# FPGA.net
KiCad netlist of a schematic drawn in Altium Designer
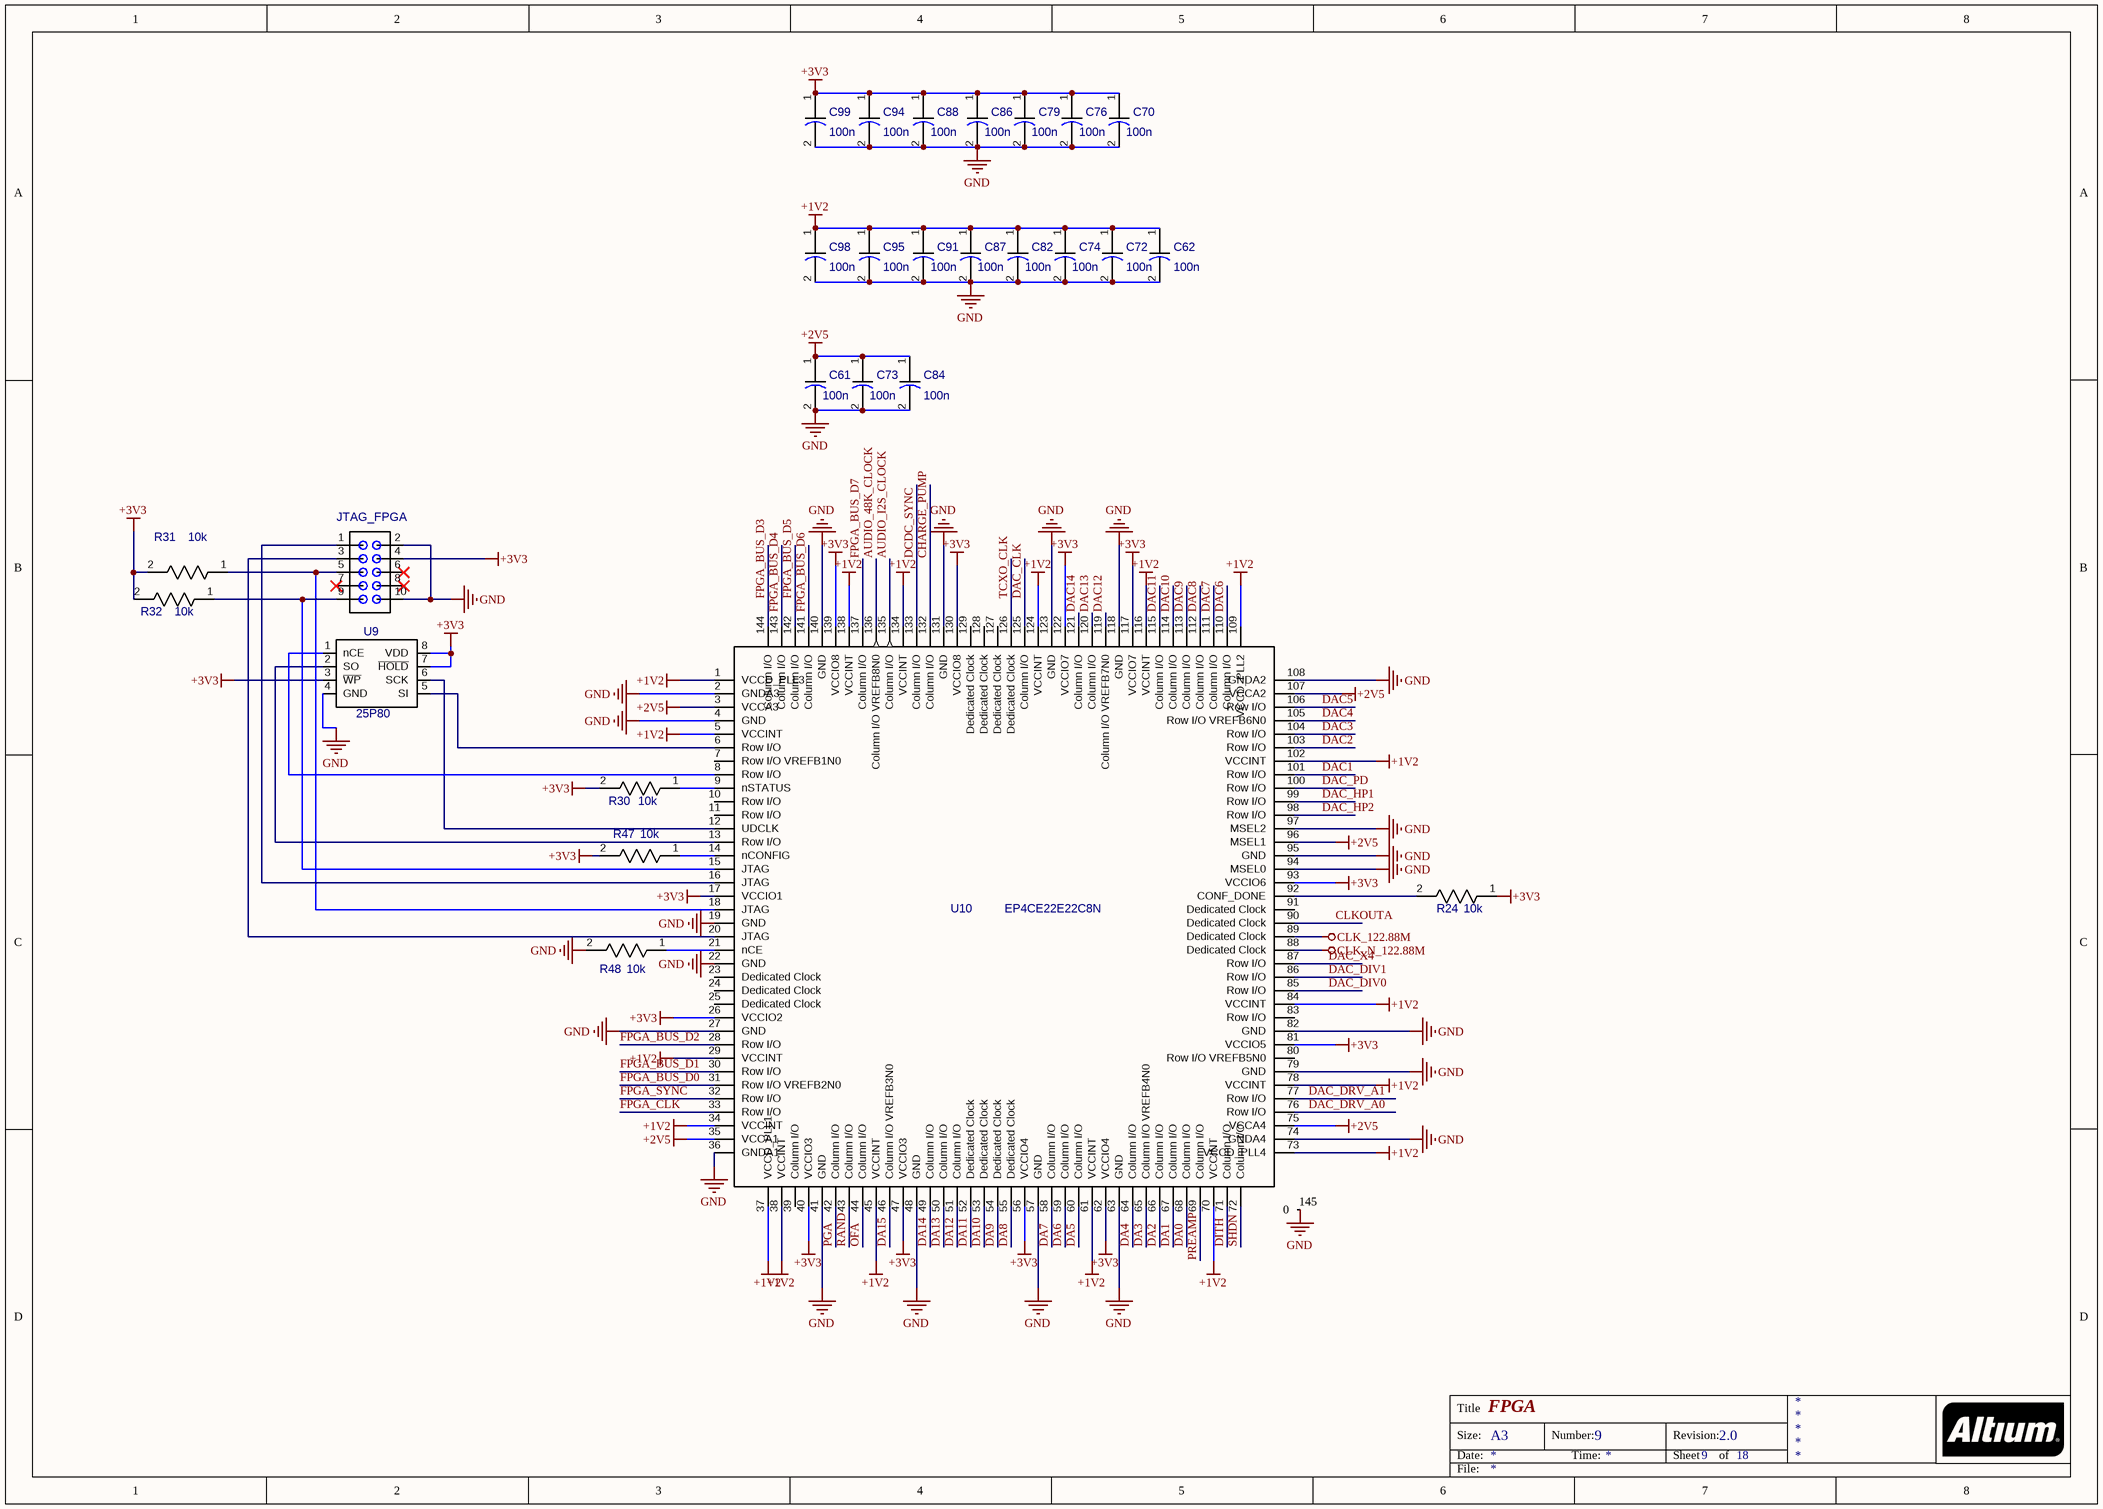
[diagram p0: FPGA.SchDoc]

(export (version "E")
  (design (tool "Eeschema 10.0.6"))
  (components
    (comp (ref "C61")
      (value "100n")
      (footprint "CAP_0805")
      (description "CAP_0805")
      (libsource (lib "*") (part "CAP_0805"))
    )
    (comp (ref "C62")
      (value "100n")
      (footprint "CAP_0805")
      (description "CAP_0805")
      (libsource (lib "*") (part "CAP_0805"))
    )
    (comp (ref "C70")
      (value "100n")
      (footprint "CAP_0805")
      (description "CAP_0805")
      (libsource (lib "*") (part "CAP_0805"))
    )
    (comp (ref "C72")
      (value "100n")
      (footprint "CAP_0805")
      (description "CAP_0805")
      (libsource (lib "*") (part "CAP_0805"))
    )
    (comp (ref "C73")
      (value "100n")
      (footprint "CAP_0805")
      (description "CAP_0805")
      (libsource (lib "*") (part "CAP_0805"))
    )
    (comp (ref "C74")
      (value "100n")
      (footprint "CAP_0805")
      (description "CAP_0805")
      (libsource (lib "*") (part "CAP_0805"))
    )
    (comp (ref "C76")
      (value "100n")
      (footprint "CAP_0805")
      (description "CAP_0805")
      (libsource (lib "*") (part "CAP_0805"))
    )
    (comp (ref "C79")
      (value "100n")
      (footprint "CAP_0805")
      (description "CAP_0805")
      (libsource (lib "*") (part "CAP_0805"))
    )
    (comp (ref "C82")
      (value "100n")
      (footprint "CAP_0805")
      (description "CAP_0805")
      (libsource (lib "*") (part "CAP_0805"))
    )
    (comp (ref "C84")
      (value "100n")
      (footprint "CAP_0805")
      (description "CAP_0805")
      (libsource (lib "*") (part "CAP_0805"))
    )
    (comp (ref "C86")
      (value "100n")
      (footprint "CAP_0805")
      (description "CAP_0805")
      (libsource (lib "*") (part "CAP_0805"))
    )
    (comp (ref "C87")
      (value "100n")
      (footprint "CAP_0805")
      (description "CAP_0805")
      (libsource (lib "*") (part "CAP_0805"))
    )
    (comp (ref "C88")
      (value "100n")
      (footprint "CAP_0805")
      (description "CAP_0805")
      (libsource (lib "*") (part "CAP_0805"))
    )
    (comp (ref "C91")
      (value "100n")
      (footprint "CAP_0805")
      (description "CAP_0805")
      (libsource (lib "*") (part "CAP_0805"))
    )
    (comp (ref "C94")
      (value "100n")
      (footprint "CAP_0805")
      (description "CAP_0805")
      (libsource (lib "*") (part "CAP_0805"))
    )
    (comp (ref "C95")
      (value "100n")
      (footprint "CAP_0805")
      (description "CAP_0805")
      (libsource (lib "*") (part "CAP_0805"))
    )
    (comp (ref "C98")
      (value "100n")
      (footprint "CAP_0805")
      (description "CAP_0805")
      (libsource (lib "*") (part "CAP_0805"))
    )
    (comp (ref "C99")
      (value "100n")
      (footprint "CAP_0805")
      (description "CAP_0805")
      (libsource (lib "*") (part "CAP_0805"))
    )
    (comp (ref "JTAG_FPGA")
      (value "~")
      (footprint "IDC10")
      (description "2*5 Pin")
      (libsource (lib "*") (part "IDC10"))
    )
    (comp (ref "R24")
      (value "10k")
      (footprint "RES_0805")
      (description "RES_0805")
      (libsource (lib "*") (part "RES_0805"))
    )
    (comp (ref "R30")
      (value "10k")
      (footprint "RES_0805")
      (description "RES_0805")
      (libsource (lib "*") (part "RES_0805"))
    )
    (comp (ref "R31")
      (value "10k")
      (footprint "RES_0805")
      (description "RES_0805")
      (libsource (lib "*") (part "RES_0805"))
    )
    (comp (ref "R32")
      (value "10k")
      (footprint "RES_0805")
      (description "RES_0805")
      (libsource (lib "*") (part "RES_0805"))
    )
    (comp (ref "R47")
      (value "10k")
      (footprint "RES_0805")
      (description "RES_0805")
      (libsource (lib "*") (part "RES_0805"))
    )
    (comp (ref "R48")
      (value "10k")
      (footprint "RES_0805")
      (description "RES_0805")
      (libsource (lib "*") (part "RES_0805"))
    )
    (comp (ref "U9") (value "25P80") (footprint "25P80") (libsource (lib "*") (part "25P80")))
    (comp (ref "U10")
      (value "EP4CE22E22C8N")
      (footprint "QFP144-20-2222A")
      (libsource (lib "*") (part "EP4CE22E22C8N"))
    )
  )
  (nets
    (net (code "1") (name "+1V2") (class "Default")
      (node (ref "C62") (pin "1") (pinfunction "1_1") (pintype "passive"))
      (node (ref "C72") (pin "1") (pinfunction "1_1") (pintype "passive"))
      (node (ref "C74") (pin "1") (pinfunction "1_1") (pintype "passive"))
      (node (ref "C82") (pin "1") (pinfunction "1_1") (pintype "passive"))
      (node (ref "C87") (pin "1") (pinfunction "1_1") (pintype "passive"))
      (node (ref "C91") (pin "1") (pinfunction "1_1") (pintype "passive"))
      (node (ref "C95") (pin "1") (pinfunction "1_1") (pintype "passive"))
      (node (ref "C98") (pin "1") (pinfunction "1_1") (pintype "passive"))
      (node (ref "U10") (pin "1") (pinfunction "VCCD_PLL3_1") (pintype "passive"))
      (node (ref "U10") (pin "102") (pinfunction "VCCINT_102") (pintype "passive"))
      (node (ref "U10") (pin "109") (pinfunction "VCCD_PLL2_109") (pintype "passive"))
      (node (ref "U10") (pin "116") (pinfunction "VCCINT_116") (pintype "passive"))
      (node (ref "U10") (pin "124") (pinfunction "VCCINT_124") (pintype "passive"))
      (node (ref "U10") (pin "134") (pinfunction "VCCINT_134") (pintype "passive"))
      (node (ref "U10") (pin "138") (pinfunction "VCCINT_138") (pintype "passive"))
      (node (ref "U10") (pin "29") (pinfunction "VCCINT_29") (pintype "passive"))
      (node (ref "U10") (pin "34") (pinfunction "VCCINT_34") (pintype "passive"))
      (node (ref "U10") (pin "37") (pinfunction "VCCD_PLL1_37") (pintype "passive"))
      (node (ref "U10") (pin "38") (pinfunction "VCCINT_38") (pintype "passive"))
      (node (ref "U10") (pin "45") (pinfunction "VCCINT_45") (pintype "passive"))
      (node (ref "U10") (pin "5") (pinfunction "VCCINT_5") (pintype "passive"))
      (node (ref "U10") (pin "61") (pinfunction "VCCINT_61") (pintype "passive"))
      (node (ref "U10") (pin "70") (pinfunction "VCCINT_70") (pintype "passive"))
      (node (ref "U10") (pin "73") (pinfunction "VCCD_PLL4_73") (pintype "passive"))
      (node (ref "U10") (pin "78") (pinfunction "VCCINT_78") (pintype "passive"))
      (node (ref "U10") (pin "84") (pinfunction "VCCINT_84") (pintype "passive"))
    )
    (net (code "2") (name "+2V5") (class "Default")
      (node (ref "C61") (pin "1") (pinfunction "1_1") (pintype "passive"))
      (node (ref "C73") (pin "1") (pinfunction "1_1") (pintype "passive"))
      (node (ref "C84") (pin "1") (pinfunction "1_1") (pintype "passive"))
      (node (ref "U10") (pin "107") (pinfunction "VCCA2_107") (pintype "passive"))
      (node (ref "U10") (pin "3") (pinfunction "VCCA3_3") (pintype "passive"))
      (node (ref "U10") (pin "35") (pinfunction "VCCA1_35") (pintype "passive"))
      (node (ref "U10") (pin "75") (pinfunction "VCCA4_75") (pintype "passive"))
      (node (ref "U10") (pin "96") (pinfunction "MSEL1_96") (pintype "passive"))
    )
    (net (code "3") (name "+3V3") (class "Default")
      (node (ref "C70") (pin "1") (pinfunction "1_1") (pintype "passive"))
      (node (ref "C76") (pin "1") (pinfunction "1_1") (pintype "passive"))
      (node (ref "C79") (pin "1") (pinfunction "1_1") (pintype "passive"))
      (node (ref "C86") (pin "1") (pinfunction "1_1") (pintype "passive"))
      (node (ref "C88") (pin "1") (pinfunction "1_1") (pintype "passive"))
      (node (ref "C94") (pin "1") (pinfunction "1_1") (pintype "passive"))
      (node (ref "C99") (pin "1") (pinfunction "1_1") (pintype "passive"))
      (node (ref "JTAG_FPGA") (pin "4") (pinfunction "4_4") (pintype "passive"))
      (node (ref "R24") (pin "1") (pinfunction "1_1") (pintype "passive"))
      (node (ref "R30") (pin "2") (pinfunction "2_2") (pintype "passive"))
      (node (ref "R31") (pin "2") (pinfunction "2_2") (pintype "passive"))
      (node (ref "R32") (pin "2") (pinfunction "2_2") (pintype "passive"))
      (node (ref "R47") (pin "2") (pinfunction "2_2") (pintype "passive"))
      (node (ref "U10") (pin "117") (pinfunction "VCCIO7_117") (pintype "passive"))
      (node (ref "U10") (pin "122") (pinfunction "VCCIO7_122") (pintype "passive"))
      (node (ref "U10") (pin "130") (pinfunction "VCCIO8_130") (pintype "passive"))
      (node (ref "U10") (pin "139") (pinfunction "VCCIO8_139") (pintype "passive"))
      (node (ref "U10") (pin "17") (pinfunction "VCCIO1_17") (pintype "passive"))
      (node (ref "U10") (pin "26") (pinfunction "VCCIO2_26") (pintype "passive"))
      (node (ref "U10") (pin "40") (pinfunction "VCCIO3_40") (pintype "passive"))
      (node (ref "U10") (pin "47") (pinfunction "VCCIO3_47") (pintype "passive"))
      (node (ref "U10") (pin "56") (pinfunction "VCCIO4_56") (pintype "passive"))
      (node (ref "U10") (pin "62") (pinfunction "VCCIO4_62") (pintype "passive"))
      (node (ref "U10") (pin "81") (pinfunction "VCCIO5_81") (pintype "passive"))
      (node (ref "U10") (pin "93") (pinfunction "VCCIO6_93") (pintype "passive"))
      (node (ref "U9") (pin "3") (pinfunction "~{WP}_3") (pintype "passive"))
      (node (ref "U9") (pin "7") (pinfunction "~{HOLD}_7") (pintype "passive"))
      (node (ref "U9") (pin "8") (pinfunction "VDD_8") (pintype "passive"))
    )
    (net (code "4") (name "/AUDIO_48K_CLOCK") (class "Default")
      (node (ref "U10") (pin "136") (pinfunction "Column_I/O_VREFB8N0_136") (pintype "output"))
    )
    (net (code "5") (name "/AUDIO_I2S_CLOCK") (class "Default")
      (node (ref "U10") (pin "135") (pinfunction "Column_I/O_135") (pintype "output"))
    )
    (net (code "6") (name "/CHARGE_PUMP") (class "Default")
      (node (ref "U10") (pin "132") (pinfunction "Column_I/O_132") (pintype "passive"))
    )
    (net (code "7") (name "/CLKOUTA") (class "Default")
      (node (ref "U10") (pin "90") (pinfunction "Dedicated_Clock_90") (pintype "passive"))
    )
    (net (code "8") (name "/DA0") (class "Default")
      (node (ref "U10") (pin "68") (pinfunction "Column_I/O_68") (pintype "passive"))
    )
    (net (code "9") (name "/DA1") (class "Default")
      (node (ref "U10") (pin "67") (pinfunction "Column_I/O_67") (pintype "passive"))
    )
    (net (code "10") (name "/DA2") (class "Default")
      (node (ref "U10") (pin "66") (pinfunction "Column_I/O_66") (pintype "passive"))
    )
    (net (code "11") (name "/DA3") (class "Default")
      (node (ref "U10") (pin "65") (pinfunction "Column_I/O_VREFB4N0_65") (pintype "passive"))
    )
    (net (code "12") (name "/DA4") (class "Default")
      (node (ref "U10") (pin "64") (pinfunction "Column_I/O_64") (pintype "passive"))
    )
    (net (code "13") (name "/DA5") (class "Default")
      (node (ref "U10") (pin "60") (pinfunction "Column_I/O_60") (pintype "passive"))
    )
    (net (code "14") (name "/DA6") (class "Default")
      (node (ref "U10") (pin "59") (pinfunction "Column_I/O_59") (pintype "passive"))
    )
    (net (code "15") (name "/DA7") (class "Default")
      (node (ref "U10") (pin "58") (pinfunction "Column_I/O_58") (pintype "passive"))
    )
    (net (code "16") (name "/DA8") (class "Default")
      (node (ref "U10") (pin "55") (pinfunction "Dedicated_Clock_55") (pintype "passive"))
    )
    (net (code "17") (name "/DA9") (class "Default")
      (node (ref "U10") (pin "54") (pinfunction "Dedicated_Clock_54") (pintype "passive"))
    )
    (net (code "18") (name "/DA10") (class "Default")
      (node (ref "U10") (pin "53") (pinfunction "Dedicated_Clock_53") (pintype "passive"))
    )
    (net (code "19") (name "/DA11") (class "Default")
      (node (ref "U10") (pin "52") (pinfunction "Dedicated_Clock_52") (pintype "passive"))
    )
    (net (code "20") (name "/DA12") (class "Default")
      (node (ref "U10") (pin "51") (pinfunction "Column_I/O_51") (pintype "passive"))
    )
    (net (code "21") (name "/DA13") (class "Default")
      (node (ref "U10") (pin "50") (pinfunction "Column_I/O_50") (pintype "passive"))
    )
    (net (code "22") (name "/DA14") (class "Default")
      (node (ref "U10") (pin "49") (pinfunction "Column_I/O_49") (pintype "passive"))
    )
    (net (code "23") (name "/DA15") (class "Default")
      (node (ref "U10") (pin "46") (pinfunction "Column_I/O_VREFB3N0_46") (pintype "passive"))
    )
    (net (code "24") (name "/DAC1") (class "Default")
      (node (ref "U10") (pin "101") (pinfunction "Row_I/O_101") (pintype "passive"))
    )
    (net (code "25") (name "/DAC2") (class "Default")
      (node (ref "U10") (pin "103") (pinfunction "Row_I/O_103") (pintype "passive"))
    )
    (net (code "26") (name "/DAC3") (class "Default")
      (node (ref "U10") (pin "104") (pinfunction "Row_I/O_104") (pintype "passive"))
    )
    (net (code "27") (name "/DAC4") (class "Default")
      (node (ref "U10") (pin "105") (pinfunction "Row_I/O_VREFB6N0_105") (pintype "passive"))
    )
    (net (code "28") (name "/DAC5") (class "Default")
      (node (ref "U10") (pin "106") (pinfunction "Row_I/O_106") (pintype "passive"))
    )
    (net (code "29") (name "/DAC6") (class "Default")
      (node (ref "U10") (pin "110") (pinfunction "Column_I/O_110") (pintype "passive"))
    )
    (net (code "30") (name "/DAC7") (class "Default")
      (node (ref "U10") (pin "111") (pinfunction "Column_I/O_111") (pintype "passive"))
    )
    (net (code "31") (name "/DAC8") (class "Default")
      (node (ref "U10") (pin "112") (pinfunction "Column_I/O_112") (pintype "passive"))
    )
    (net (code "32") (name "/DAC9") (class "Default")
      (node (ref "U10") (pin "113") (pinfunction "Column_I/O_113") (pintype "passive"))
    )
    (net (code "33") (name "/DAC10") (class "Default")
      (node (ref "U10") (pin "114") (pinfunction "Column_I/O_114") (pintype "passive"))
    )
    (net (code "34") (name "/DAC11") (class "Default")
      (node (ref "U10") (pin "115") (pinfunction "Column_I/O_115") (pintype "passive"))
    )
    (net (code "35") (name "/DAC12") (class "Default")
      (node (ref "U10") (pin "119") (pinfunction "Column_I/O_VREFB7N0_119") (pintype "passive"))
    )
    (net (code "36") (name "/DAC13") (class "Default")
      (node (ref "U10") (pin "120") (pinfunction "Column_I/O_120") (pintype "passive"))
    )
    (net (code "37") (name "/DAC14") (class "Default")
      (node (ref "U10") (pin "121") (pinfunction "Column_I/O_121") (pintype "passive"))
    )
    (net (code "38") (name "/DAC_CLK") (class "Default")
      (node (ref "U10") (pin "125") (pinfunction "Column_I/O_125") (pintype "passive"))
    )
    (net (code "39") (name "/DAC_DIV0") (class "Default")
      (node (ref "U10") (pin "85") (pinfunction "Row_I/O_85") (pintype "passive"))
    )
    (net (code "40") (name "/DAC_DIV1") (class "Default")
      (node (ref "U10") (pin "86") (pinfunction "Row_I/O_86") (pintype "passive"))
    )
    (net (code "41") (name "/DAC_DRV_A0") (class "Default")
      (node (ref "U10") (pin "76") (pinfunction "Row_I/O_76") (pintype "passive"))
    )
    (net (code "42") (name "/DAC_DRV_A1") (class "Default")
      (node (ref "U10") (pin "77") (pinfunction "Row_I/O_77") (pintype "passive"))
    )
    (net (code "43") (name "/DAC_HP1") (class "Default")
      (node (ref "U10") (pin "99") (pinfunction "Row_I/O_99") (pintype "passive"))
    )
    (net (code "44") (name "/DAC_HP2") (class "Default")
      (node (ref "U10") (pin "98") (pinfunction "Row_I/O_98") (pintype "passive"))
    )
    (net (code "45") (name "/DAC_PD") (class "Default")
      (node (ref "U10") (pin "100") (pinfunction "Row_I/O_100") (pintype "passive"))
    )
    (net (code "46") (name "/DAC_X4") (class "Default")
      (node (ref "U10") (pin "87") (pinfunction "Row_I/O_87") (pintype "passive"))
    )
    (net (code "47") (name "/DCDC_SYNC") (class "Default")
      (node (ref "U10") (pin "133") (pinfunction "Column_I/O_133") (pintype "passive"))
    )
    (net (code "48") (name "/DITH") (class "Default")
      (node (ref "U10") (pin "71") (pinfunction "Column_I/O_71") (pintype "passive"))
    )
    (net (code "49") (name "/FPGA_BUS_D0") (class "Default")
      (node (ref "U10") (pin "31") (pinfunction "Row_I/O_VREFB2N0_31") (pintype "passive"))
    )
    (net (code "50") (name "/FPGA_BUS_D1") (class "Default")
      (node (ref "U10") (pin "30") (pinfunction "Row_I/O_30") (pintype "passive"))
    )
    (net (code "51") (name "/FPGA_BUS_D2") (class "Default")
      (node (ref "U10") (pin "28") (pinfunction "Row_I/O_28") (pintype "passive"))
    )
    (net (code "52") (name "/FPGA_BUS_D3") (class "Default")
      (node (ref "U10") (pin "144") (pinfunction "Column_I/O_144") (pintype "passive"))
    )
    (net (code "53") (name "/FPGA_BUS_D4") (class "Default")
      (node (ref "U10") (pin "143") (pinfunction "Column_I/O_143") (pintype "passive"))
    )
    (net (code "54") (name "/FPGA_BUS_D5") (class "Default")
      (node (ref "U10") (pin "142") (pinfunction "Column_I/O_142") (pintype "passive"))
    )
    (net (code "55") (name "/FPGA_BUS_D6") (class "Default")
      (node (ref "U10") (pin "141") (pinfunction "Column_I/O_141") (pintype "passive"))
    )
    (net (code "56") (name "/FPGA_BUS_D7") (class "Default")
      (node (ref "U10") (pin "137") (pinfunction "Column_I/O_137") (pintype "passive"))
    )
    (net (code "57") (name "/FPGA_CLK") (class "Default")
      (node (ref "U10") (pin "33") (pinfunction "Row_I/O_33") (pintype "passive"))
    )
    (net (code "58") (name "/FPGA_SYNC") (class "Default")
      (node (ref "U10") (pin "32") (pinfunction "Row_I/O_32") (pintype "passive"))
    )
    (net (code "59") (name "/OFA") (class "Default")
      (node (ref "U10") (pin "44") (pinfunction "Column_I/O_44") (pintype "passive"))
    )
    (net (code "60") (name "/PGA") (class "Default")
      (node (ref "U10") (pin "42") (pinfunction "Column_I/O_42") (pintype "passive"))
    )
    (net (code "61") (name "/PREAMP") (class "Default")
      (node (ref "U10") (pin "69") (pinfunction "Column_I/O_69") (pintype "passive"))
    )
    (net (code "62") (name "/RAND") (class "Default")
      (node (ref "U10") (pin "43") (pinfunction "Column_I/O_43") (pintype "passive"))
    )
    (net (code "63") (name "/SHDN") (class "Default")
      (node (ref "U10") (pin "72") (pinfunction "Column_I/O_72") (pintype "passive"))
    )
    (net (code "64") (name "/TCXO_CLK") (class "Default")
      (node (ref "U10") (pin "126") (pinfunction "Dedicated_Clock_126") (pintype "passive"))
    )
    (net (code "65") (name "CLK_122.88M") (class "Default")
      (node (ref "U10") (pin "89") (pinfunction "Dedicated_Clock_89") (pintype "passive"))
    )
    (net (code "66") (name "CLK_N_122.88M") (class "Default")
      (node (ref "U10") (pin "88") (pinfunction "Dedicated_Clock_88") (pintype "passive"))
    )
    (net (code "67") (name "GND") (class "Default")
      (node (ref "C61") (pin "2") (pinfunction "2_2") (pintype "passive"))
      (node (ref "C62") (pin "2") (pinfunction "2_2") (pintype "passive"))
      (node (ref "C70") (pin "2") (pinfunction "2_2") (pintype "passive"))
      (node (ref "C72") (pin "2") (pinfunction "2_2") (pintype "passive"))
      (node (ref "C73") (pin "2") (pinfunction "2_2") (pintype "passive"))
      (node (ref "C74") (pin "2") (pinfunction "2_2") (pintype "passive"))
      (node (ref "C76") (pin "2") (pinfunction "2_2") (pintype "passive"))
      (node (ref "C79") (pin "2") (pinfunction "2_2") (pintype "passive"))
      (node (ref "C82") (pin "2") (pinfunction "2_2") (pintype "passive"))
      (node (ref "C84") (pin "2") (pinfunction "2_2") (pintype "passive"))
      (node (ref "C86") (pin "2") (pinfunction "2_2") (pintype "passive"))
      (node (ref "C87") (pin "2") (pinfunction "2_2") (pintype "passive"))
      (node (ref "C88") (pin "2") (pinfunction "2_2") (pintype "passive"))
      (node (ref "C91") (pin "2") (pinfunction "2_2") (pintype "passive"))
      (node (ref "C94") (pin "2") (pinfunction "2_2") (pintype "passive"))
      (node (ref "C95") (pin "2") (pinfunction "2_2") (pintype "passive"))
      (node (ref "C98") (pin "2") (pinfunction "2_2") (pintype "passive"))
      (node (ref "C99") (pin "2") (pinfunction "2_2") (pintype "passive"))
      (node (ref "JTAG_FPGA") (pin "10") (pinfunction "10_10") (pintype "passive"))
      (node (ref "JTAG_FPGA") (pin "2") (pinfunction "2_2") (pintype "passive"))
      (node (ref "R48") (pin "2") (pinfunction "2_2") (pintype "passive"))
      (node (ref "U10") (pin "108") (pinfunction "GNDA2_108") (pintype "passive"))
      (node (ref "U10") (pin "118") (pinfunction "GND_118") (pintype "passive"))
      (node (ref "U10") (pin "123") (pinfunction "GND_123") (pintype "passive"))
      (node (ref "U10") (pin "131") (pinfunction "GND_131") (pintype "passive"))
      (node (ref "U10") (pin "140") (pinfunction "GND_140") (pintype "passive"))
      (node (ref "U10") (pin "145") (pinfunction "0_145") (pintype "passive"))
      (node (ref "U10") (pin "19") (pinfunction "GND_19") (pintype "passive"))
      (node (ref "U10") (pin "2") (pinfunction "GNDA3_2") (pintype "passive"))
      (node (ref "U10") (pin "22") (pinfunction "GND_22") (pintype "passive"))
      (node (ref "U10") (pin "27") (pinfunction "GND_27") (pintype "passive"))
      (node (ref "U10") (pin "36") (pinfunction "GNDA1_36") (pintype "passive"))
      (node (ref "U10") (pin "4") (pinfunction "GND_4") (pintype "passive"))
      (node (ref "U10") (pin "41") (pinfunction "GND_41") (pintype "passive"))
      (node (ref "U10") (pin "48") (pinfunction "GND_48") (pintype "passive"))
      (node (ref "U10") (pin "57") (pinfunction "GND_57") (pintype "passive"))
      (node (ref "U10") (pin "63") (pinfunction "GND_63") (pintype "passive"))
      (node (ref "U10") (pin "74") (pinfunction "GNDA4_74") (pintype "passive"))
      (node (ref "U10") (pin "79") (pinfunction "GND_79") (pintype "passive"))
      (node (ref "U10") (pin "82") (pinfunction "GND_82") (pintype "passive"))
      (node (ref "U10") (pin "94") (pinfunction "MSEL0_94") (pintype "passive"))
      (node (ref "U10") (pin "95") (pinfunction "GND_95") (pintype "passive"))
      (node (ref "U10") (pin "97") (pinfunction "MSEL2_97") (pintype "passive"))
      (node (ref "U9") (pin "4") (pinfunction "GND_4") (pintype "passive"))
    )
    (net (code "68") (name "Net-(JTAG_FPGA-Pad1)") (class "Default")
      (node (ref "JTAG_FPGA") (pin "1") (pinfunction "1_1") (pintype "passive"))
      (node (ref "U10") (pin "16") (pinfunction "JTAG_16") (pintype "passive"))
    )
    (net (code "69") (name "Net-(JTAG_FPGA-Pad3)") (class "Default")
      (node (ref "JTAG_FPGA") (pin "3") (pinfunction "3_3") (pintype "passive"))
      (node (ref "U10") (pin "20") (pinfunction "JTAG_20") (pintype "passive"))
    )
    (net (code "70") (name "Net-(JTAG_FPGA-Pad5)") (class "Default")
      (node (ref "JTAG_FPGA") (pin "5") (pinfunction "5_5") (pintype "passive"))
      (node (ref "R31") (pin "1") (pinfunction "1_1") (pintype "passive"))
      (node (ref "U10") (pin "18") (pinfunction "JTAG_18") (pintype "passive"))
    )
    (net (code "71") (name "Net-(JTAG_FPGA-Pad9)") (class "Default")
      (node (ref "JTAG_FPGA") (pin "9") (pinfunction "9_9") (pintype "passive"))
      (node (ref "R32") (pin "1") (pinfunction "1_1") (pintype "passive"))
      (node (ref "U10") (pin "15") (pinfunction "JTAG_15") (pintype "passive"))
    )
    (net (code "72") (name "Net-(U9-SI)") (class "Default")
      (node (ref "U10") (pin "6") (pinfunction "Row_I/O_6") (pintype "passive"))
      (node (ref "U9") (pin "5") (pinfunction "SI_5") (pintype "passive"))
    )
    (net (code "73") (name "Net-(U9-SO)") (class "Default")
      (node (ref "U10") (pin "13") (pinfunction "Row_I/O_13") (pintype "passive"))
      (node (ref "U9") (pin "2") (pinfunction "SO_2") (pintype "passive"))
    )
    (net (code "74") (name "Net-(U9-nCE)") (class "Default")
      (node (ref "U10") (pin "8") (pinfunction "Row_I/O_8") (pintype "passive"))
      (node (ref "U9") (pin "1") (pinfunction "nCE_1") (pintype "passive"))
    )
    (net (code "75") (name "Net-(U10-CONF_DONE)") (class "Default")
      (node (ref "R24") (pin "2") (pinfunction "2_2") (pintype "passive"))
      (node (ref "U10") (pin "92") (pinfunction "CONF_DONE_92") (pintype "passive"))
    )
    (net (code "76") (name "Net-(U10-UDCLK)") (class "Default")
      (node (ref "U10") (pin "12") (pinfunction "UDCLK_12") (pintype "passive"))
      (node (ref "U9") (pin "6") (pinfunction "SCK_6") (pintype "passive"))
    )
    (net (code "77") (name "Net-(U10-nCE)") (class "Default")
      (node (ref "R48") (pin "1") (pinfunction "1_1") (pintype "passive"))
      (node (ref "U10") (pin "21") (pinfunction "nCE_21") (pintype "passive"))
    )
    (net (code "78") (name "Net-(U10-nCONFIG)") (class "Default")
      (node (ref "R47") (pin "1") (pinfunction "1_1") (pintype "passive"))
      (node (ref "U10") (pin "14") (pinfunction "nCONFIG_14") (pintype "passive"))
    )
    (net (code "79") (name "Net-(U10-nSTATUS)") (class "Default")
      (node (ref "R30") (pin "1") (pinfunction "1_1") (pintype "passive"))
      (node (ref "U10") (pin "9") (pinfunction "nSTATUS_9") (pintype "passive"))
    )
    (net (code "80") (name "unconnected-(JTAG_FPGA-Pad6)") (class "Default")
      (node (ref "JTAG_FPGA") (pin "6") (pinfunction "6_6") (pintype "passive+no_connect"))
    )
    (net (code "81") (name "unconnected-(JTAG_FPGA-Pad7)") (class "Default")
      (node (ref "JTAG_FPGA") (pin "7") (pinfunction "7_7") (pintype "passive+no_connect"))
    )
    (net (code "82") (name "unconnected-(JTAG_FPGA-Pad8)") (class "Default")
      (node (ref "JTAG_FPGA") (pin "8") (pinfunction "8_8") (pintype "passive+no_connect"))
    )
    (net (code "83") (name "unconnected-(U10-Column_I{slash}O-Pad39)") (class "Default")
      (node (ref "U10") (pin "39") (pinfunction "Column_I/O_39") (pintype "passive"))
    )
    (net (code "84") (name "unconnected-(U10-Dedicated_Clock-Pad23)") (class "Default")
      (node (ref "U10") (pin "23") (pinfunction "Dedicated_Clock_23") (pintype "passive"))
    )
    (net (code "85") (name "unconnected-(U10-Dedicated_Clock-Pad24)") (class "Default")
      (node (ref "U10") (pin "24") (pinfunction "Dedicated_Clock_24") (pintype "passive"))
    )
    (net (code "86") (name "unconnected-(U10-Dedicated_Clock-Pad25)") (class "Default")
      (node (ref "U10") (pin "25") (pinfunction "Dedicated_Clock_25") (pintype "passive"))
    )
    (net (code "87") (name "unconnected-(U10-Dedicated_Clock-Pad91)") (class "Default")
      (node (ref "U10") (pin "91") (pinfunction "Dedicated_Clock_91") (pintype "passive"))
    )
    (net (code "88") (name "unconnected-(U10-Dedicated_Clock-Pad127)") (class "Default")
      (node (ref "U10") (pin "127") (pinfunction "Dedicated_Clock_127") (pintype "passive"))
    )
    (net (code "89") (name "unconnected-(U10-Dedicated_Clock-Pad128)") (class "Default")
      (node (ref "U10") (pin "128") (pinfunction "Dedicated_Clock_128") (pintype "passive"))
    )
    (net (code "90") (name "unconnected-(U10-Dedicated_Clock-Pad129)") (class "Default")
      (node (ref "U10") (pin "129") (pinfunction "Dedicated_Clock_129") (pintype "passive"))
    )
    (net (code "91") (name "unconnected-(U10-Row_I{slash}O-Pad10)") (class "Default")
      (node (ref "U10") (pin "10") (pinfunction "Row_I/O_10") (pintype "passive"))
    )
    (net (code "92") (name "unconnected-(U10-Row_I{slash}O-Pad11)") (class "Default")
      (node (ref "U10") (pin "11") (pinfunction "Row_I/O_11") (pintype "passive"))
    )
    (net (code "93") (name "unconnected-(U10-Row_I{slash}O-Pad83)") (class "Default")
      (node (ref "U10") (pin "83") (pinfunction "Row_I/O_83") (pintype "passive"))
    )
    (net (code "94") (name "unconnected-(U10-Row_I{slash}O_VREFB1N0-Pad7)") (class "Default")
      (node (ref "U10") (pin "7") (pinfunction "Row_I/O_VREFB1N0_7") (pintype "passive"))
    )
    (net (code "95") (name "unconnected-(U10-Row_I{slash}O_VREFB5N0-Pad80)") (class "Default")
      (node (ref "U10") (pin "80") (pinfunction "Row_I/O_VREFB5N0_80") (pintype "passive"))
    )
  )
)
